# MRCS_ANIMATION-CONTROLLER.net
KiCad netlist of a schematic drawn in EAGLE
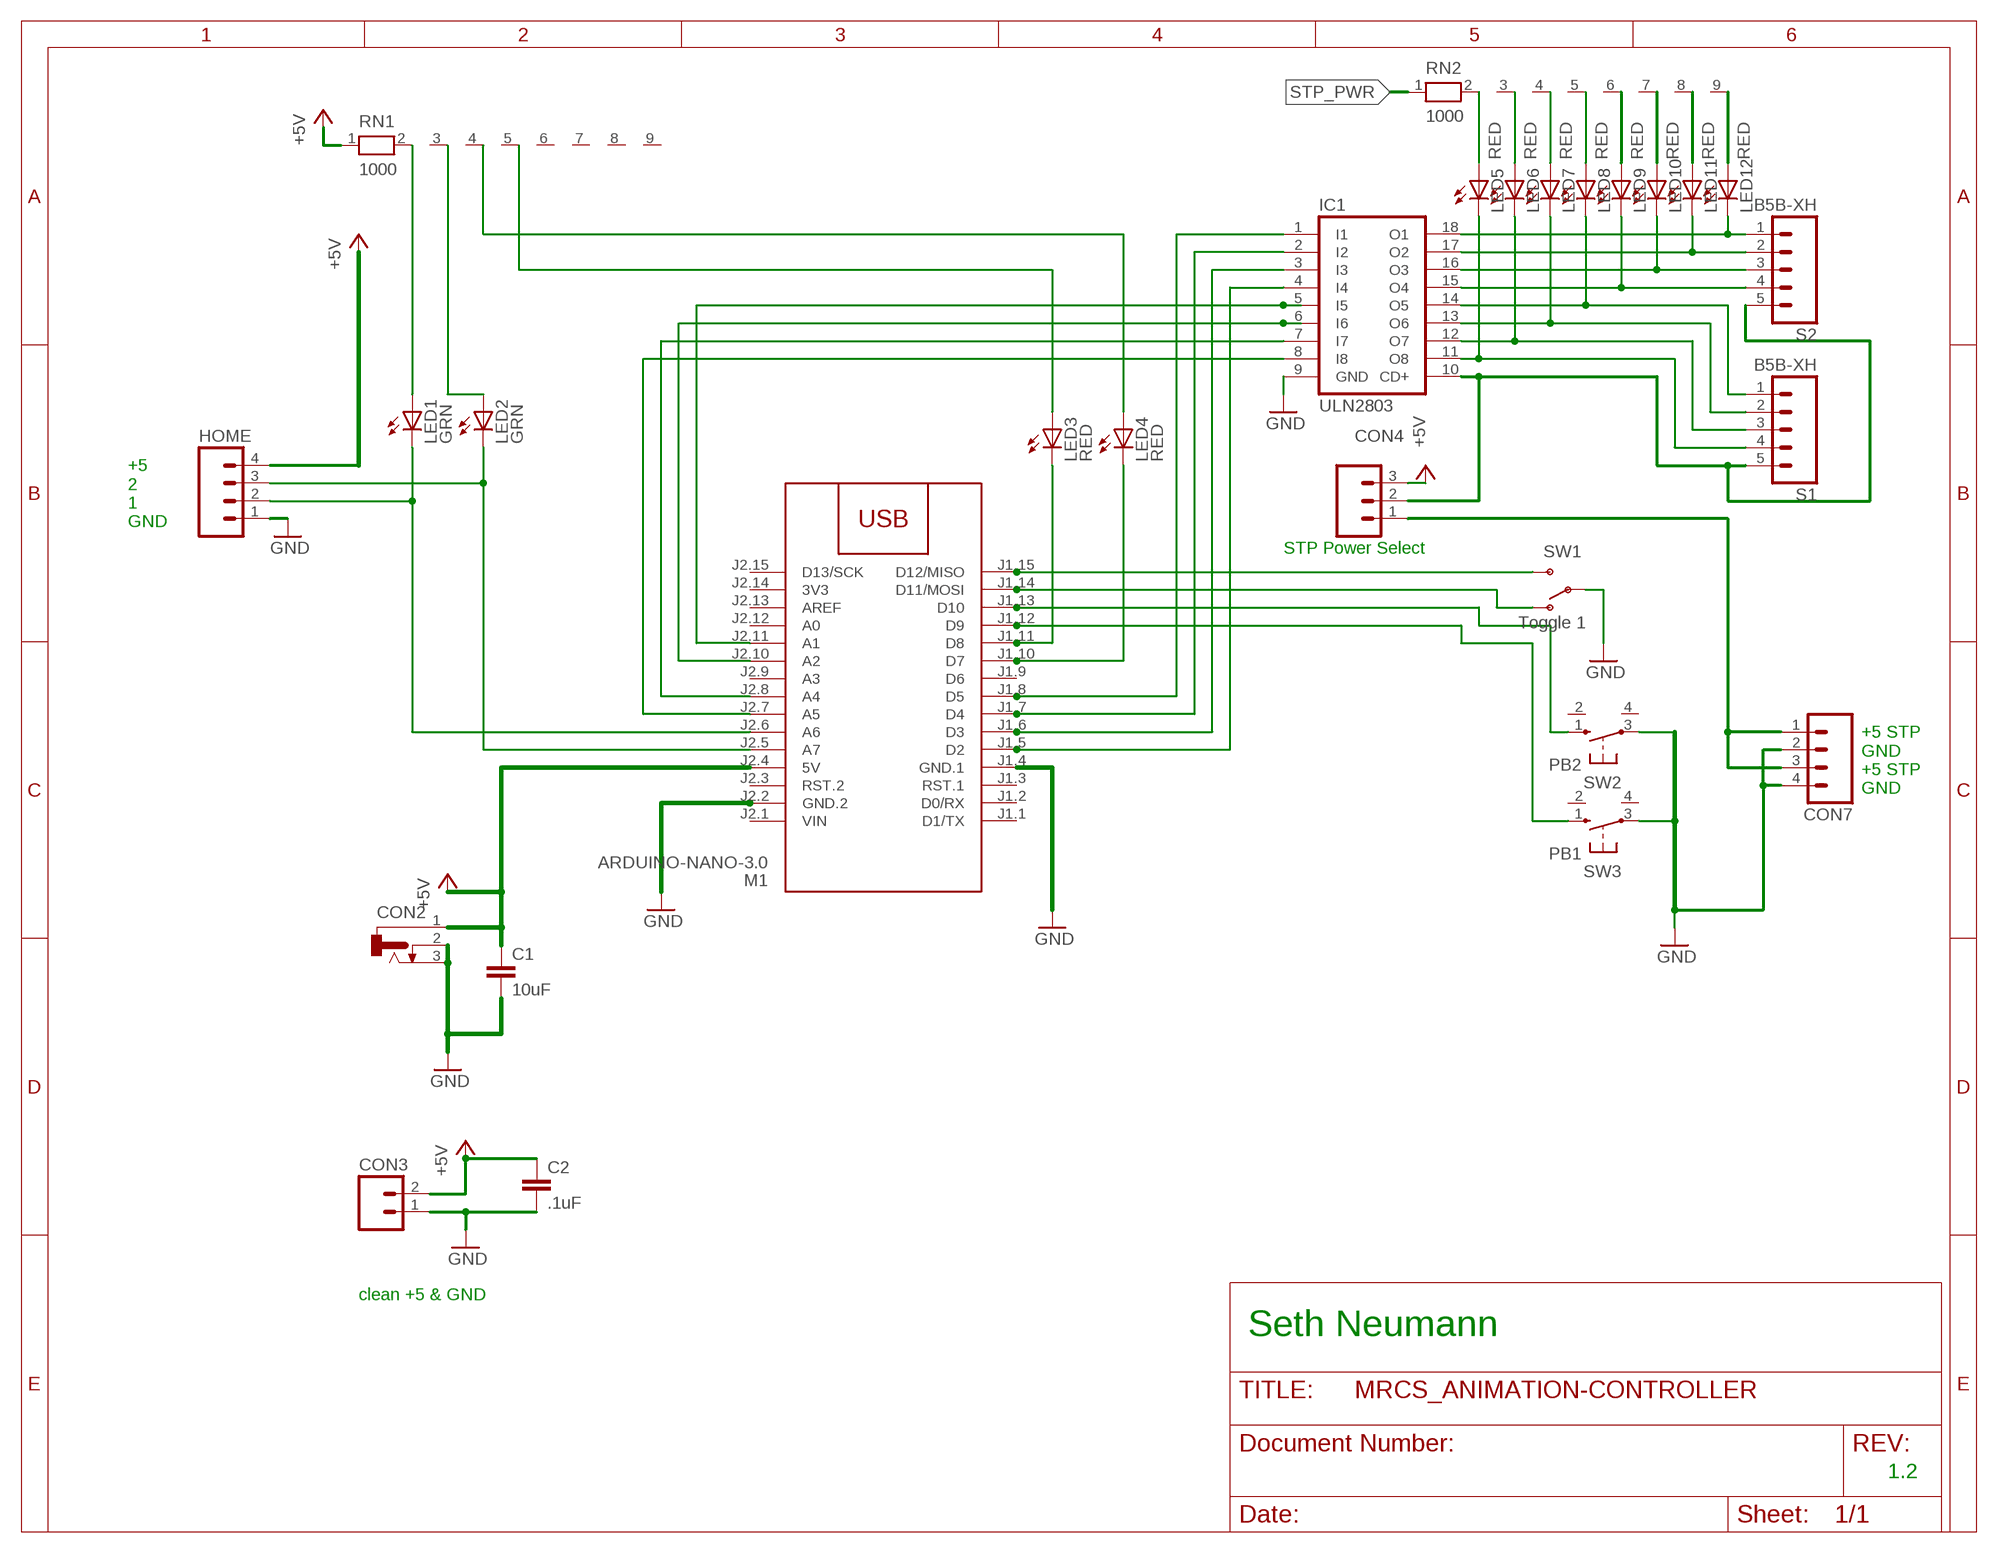
[diagram p0: schematic, sheet 1]

(export (version "E")
  (design (tool "Eeschema 10.0.6"))
  (components
    (comp (ref "C1")
      (value "10uF")
      (footprint "eagle-import:C5B3")
      (libsource (lib "eagle-import") (part "C5/3"))
    )
    (comp (ref "C2")
      (value ".1uF")
      (footprint "eagle-import:C5B3")
      (libsource (lib "eagle-import") (part "C5/3"))
    )
    (comp (ref "CON2")
      (value "CONNECTOR-DC-POWER-RA")
      (footprint "eagle-import:DCJ0202")
      (libsource (lib "eagle-import") (part "CONNECTOR-DC-POWER-RA"))
    )
    (comp (ref "CON3")
      (value "CONNECTOR-M02350-LOCK")
      (footprint "eagle-import:1751248")
      (libsource (lib "eagle-import") (part "CONNECTOR-M02350-LOCK"))
    )
    (comp (ref "CON4")
      (value "CONNECTOR-M03254-LOCK")
      (footprint "eagle-import:3POL254")
      (libsource (lib "eagle-import") (part "CONNECTOR-M03254-LOCK"))
    )
    (comp (ref "CON7")
      (value "CONNECTOR-M04SCREW_LOCK")
      (footprint "eagle-import:SCREWTERMINAL-3.5MM-4_LOCK")
      (libsource (lib "eagle-import") (part "CONNECTOR-M04SCREW_LOCK"))
    )
    (comp (ref "HOME")
      (value "CONNECTOR-M04LOCK")
      (footprint "eagle-import:1X04_LOCK")
      (libsource (lib "eagle-import") (part "CONNECTOR-M04LOCK"))
    )
    (comp (ref "IC1")
      (value "ULN2803")
      (footprint "eagle-import:DIL18")
      (libsource (lib "eagle-import") (part "ULN2803A"))
    )
    (comp (ref "LED1")
      (value "GRN")
      (footprint "eagle-import:LED3MM")
      (libsource (lib "eagle-import") (part "LEDLED3MM"))
    )
    (comp (ref "LED2")
      (value "GRN")
      (footprint "eagle-import:LED3MM")
      (libsource (lib "eagle-import") (part "LEDLED3MM"))
    )
    (comp (ref "LED3")
      (value "RED")
      (footprint "eagle-import:LED3MM")
      (libsource (lib "eagle-import") (part "LEDLED3MM"))
    )
    (comp (ref "LED4")
      (value "RED")
      (footprint "eagle-import:LED3MM")
      (libsource (lib "eagle-import") (part "LEDLED3MM"))
    )
    (comp (ref "LED5")
      (value "RED")
      (footprint "eagle-import:LED3MM")
      (libsource (lib "eagle-import") (part "LEDLED3MM"))
    )
    (comp (ref "LED6")
      (value "RED")
      (footprint "eagle-import:LED3MM")
      (libsource (lib "eagle-import") (part "LEDLED3MM"))
    )
    (comp (ref "LED7")
      (value "RED")
      (footprint "eagle-import:LED3MM")
      (libsource (lib "eagle-import") (part "LEDLED3MM"))
    )
    (comp (ref "LED8")
      (value "RED")
      (footprint "eagle-import:LED3MM")
      (libsource (lib "eagle-import") (part "LEDLED3MM"))
    )
    (comp (ref "LED9")
      (value "RED")
      (footprint "eagle-import:LED3MM")
      (libsource (lib "eagle-import") (part "LEDLED3MM"))
    )
    (comp (ref "LED10")
      (value "RED")
      (footprint "eagle-import:LED3MM")
      (libsource (lib "eagle-import") (part "LEDLED3MM"))
    )
    (comp (ref "LED11")
      (value "RED")
      (footprint "eagle-import:LED3MM")
      (libsource (lib "eagle-import") (part "LEDLED3MM"))
    )
    (comp (ref "LED12")
      (value "RED")
      (footprint "eagle-import:LED3MM")
      (libsource (lib "eagle-import") (part "LEDLED3MM"))
    )
    (comp (ref "M1")
      (value "ARDUINO-NANO-3.0")
      (footprint "eagle-import:ARDUINO-NANO-3.0")
      (libsource (lib "eagle-import") (part "ARDUINO-NANO-3.0"))
    )
    (comp (ref "RN1")
      (value "1000")
      (footprint "eagle-import:RN-9")
      (libsource (lib "eagle-import") (part "RN08"))
    )
    (comp (ref "RN2")
      (value "1000")
      (footprint "eagle-import:RN-9")
      (libsource (lib "eagle-import") (part "RN08"))
    )
    (comp (ref "S1")
      (value "B5B-XH")
      (footprint "eagle-import:1X05_LOCK")
      (libsource (lib "eagle-import") (part "CONNECTOR-M05LOCK"))
    )
    (comp (ref "S2")
      (value "B5B-XH")
      (footprint "eagle-import:1X05_LOCK")
      (libsource (lib "eagle-import") (part "CONNECTOR-M05LOCK"))
    )
    (comp (ref "SW1")
      (value "Toggle 1")
      (footprint "eagle-import:SWITCH-SPDT-508")
      (libsource (lib "eagle-import") (part "SWITCH-SPSTPTH-508"))
    )
    (comp (ref "SW2")
      (value "PB2")
      (footprint "eagle-import:4P-PTH-6.0X6.0X5.0H")
      (libsource (lib "eagle-import") (part "SWITCH-(ON)SMALLPADS"))
    )
    (comp (ref "SW3")
      (value "PB1")
      (footprint "eagle-import:4P-PTH-6.0X6.0X5.0H")
      (libsource (lib "eagle-import") (part "SWITCH-(ON)SMALLPADS"))
    )
  )
  (nets
    (net (code "1") (name "+5V") (class "Default")
      (node (ref "C1") (pin "1") (pinfunction "1_1") (pintype "passive"))
      (node (ref "C2") (pin "1") (pinfunction "1_1") (pintype "passive"))
      (node (ref "CON2") (pin "1") (pinfunction "1_1") (pintype "passive"))
      (node (ref "CON3") (pin "2") (pinfunction "B_2") (pintype "passive"))
      (node (ref "CON4") (pin "3") (pinfunction "3_3") (pintype "passive"))
      (node (ref "HOME") (pin "4") (pinfunction "4_4") (pintype "passive"))
      (node (ref "M1") (pin "J2.4") (pinfunction "5V_J2.4") (pintype "power_in"))
      (node (ref "RN1") (pin "1") (pinfunction "1_1") (pintype "passive"))
    )
    (net (code "2") (name "/3V3") (class "Default")
      (node (ref "M1") (pin "J2.14") (pinfunction "3V3_J2.14") (pintype "power_in"))
    )
    (net (code "3") (name "/VIN") (class "Default")
      (node (ref "M1") (pin "J2.1") (pinfunction "VIN_J2.1") (pintype "power_in"))
    )
    (net (code "4") (name "GND") (class "Default")
      (node (ref "C1") (pin "2") (pinfunction "2_2") (pintype "passive"))
      (node (ref "C2") (pin "2") (pinfunction "2_2") (pintype "passive"))
      (node (ref "CON2") (pin "2") (pinfunction "2_2") (pintype "passive"))
      (node (ref "CON2") (pin "3") (pinfunction "3_3") (pintype "passive"))
      (node (ref "CON3") (pin "1") (pinfunction "A_1") (pintype "passive"))
      (node (ref "CON7") (pin "2") (pinfunction "2_2") (pintype "passive"))
      (node (ref "CON7") (pin "4") (pinfunction "4_4") (pintype "passive"))
      (node (ref "HOME") (pin "1") (pinfunction "1_1") (pintype "passive"))
      (node (ref "IC1") (pin "9") (pinfunction "GND_9") (pintype "power_in"))
      (node (ref "M1") (pin "J1.4") (pinfunction "GND.1_J1.4") (pintype "power_in"))
      (node (ref "M1") (pin "J2.2") (pinfunction "GND.2_J2.2") (pintype "power_in"))
      (node (ref "SW1") (pin "2") (pinfunction "P_2") (pintype "passive"))
      (node (ref "SW2") (pin "3") (pinfunction "P_3") (pintype "passive"))
      (node (ref "SW3") (pin "3") (pinfunction "P_3") (pintype "passive"))
    )
    (net (code "5") (name "Net-(CON4-Pad1)") (class "Default")
      (node (ref "CON4") (pin "1") (pinfunction "1_1") (pintype "passive"))
      (node (ref "CON7") (pin "1") (pinfunction "1_1") (pintype "passive"))
      (node (ref "CON7") (pin "3") (pinfunction "3_3") (pintype "passive"))
    )
    (net (code "6") (name "Net-(IC1-I1)") (class "Default")
      (node (ref "IC1") (pin "1") (pinfunction "I1_1") (pintype "input"))
      (node (ref "M1") (pin "J1.8") (pinfunction "D5_J1.8") (pintype "bidirectional"))
    )
    (net (code "7") (name "Net-(IC1-I2)") (class "Default")
      (node (ref "IC1") (pin "2") (pinfunction "I2_2") (pintype "input"))
      (node (ref "M1") (pin "J1.7") (pinfunction "D4_J1.7") (pintype "bidirectional"))
    )
    (net (code "8") (name "Net-(IC1-I3)") (class "Default")
      (node (ref "IC1") (pin "3") (pinfunction "I3_3") (pintype "input"))
      (node (ref "M1") (pin "J1.6") (pinfunction "D3_J1.6") (pintype "bidirectional"))
    )
    (net (code "9") (name "Net-(IC1-I4)") (class "Default")
      (node (ref "IC1") (pin "4") (pinfunction "I4_4") (pintype "input"))
      (node (ref "M1") (pin "J1.5") (pinfunction "D2_J1.5") (pintype "bidirectional"))
    )
    (net (code "10") (name "Net-(IC1-I5)") (class "Default")
      (node (ref "IC1") (pin "5") (pinfunction "I5_5") (pintype "input"))
      (node (ref "M1") (pin "J2.11") (pinfunction "A1_J2.11") (pintype "bidirectional"))
    )
    (net (code "11") (name "Net-(IC1-I6)") (class "Default")
      (node (ref "IC1") (pin "6") (pinfunction "I6_6") (pintype "input"))
      (node (ref "M1") (pin "J2.10") (pinfunction "A2_J2.10") (pintype "bidirectional"))
    )
    (net (code "12") (name "Net-(IC1-I7)") (class "Default")
      (node (ref "IC1") (pin "7") (pinfunction "I7_7") (pintype "input"))
      (node (ref "M1") (pin "J2.8") (pinfunction "A4_J2.8") (pintype "bidirectional"))
    )
    (net (code "13") (name "Net-(IC1-I8)") (class "Default")
      (node (ref "IC1") (pin "8") (pinfunction "I8_8") (pintype "input"))
      (node (ref "M1") (pin "J2.7") (pinfunction "A5_J2.7") (pintype "bidirectional"))
    )
    (net (code "14") (name "Net-(IC1-O1)") (class "Default")
      (node (ref "IC1") (pin "18") (pinfunction "O1_18") (pintype "open_collector"))
      (node (ref "LED12") (pin "K") (pinfunction "C_K") (pintype "passive"))
      (node (ref "S2") (pin "1") (pinfunction "1_1") (pintype "passive"))
    )
    (net (code "15") (name "Net-(IC1-O2)") (class "Default")
      (node (ref "IC1") (pin "17") (pinfunction "O2_17") (pintype "open_collector"))
      (node (ref "LED11") (pin "K") (pinfunction "C_K") (pintype "passive"))
      (node (ref "S2") (pin "2") (pinfunction "2_2") (pintype "passive"))
    )
    (net (code "16") (name "Net-(IC1-O3)") (class "Default")
      (node (ref "IC1") (pin "16") (pinfunction "O3_16") (pintype "open_collector"))
      (node (ref "LED10") (pin "K") (pinfunction "C_K") (pintype "passive"))
      (node (ref "S2") (pin "3") (pinfunction "3_3") (pintype "passive"))
    )
    (net (code "17") (name "Net-(IC1-O4)") (class "Default")
      (node (ref "IC1") (pin "15") (pinfunction "O4_15") (pintype "open_collector"))
      (node (ref "LED9") (pin "K") (pinfunction "C_K") (pintype "passive"))
      (node (ref "S2") (pin "4") (pinfunction "4_4") (pintype "passive"))
    )
    (net (code "18") (name "Net-(IC1-O5)") (class "Default")
      (node (ref "IC1") (pin "14") (pinfunction "O5_14") (pintype "open_collector"))
      (node (ref "LED8") (pin "K") (pinfunction "C_K") (pintype "passive"))
      (node (ref "S1") (pin "1") (pinfunction "1_1") (pintype "passive"))
    )
    (net (code "19") (name "Net-(IC1-O6)") (class "Default")
      (node (ref "IC1") (pin "13") (pinfunction "O6_13") (pintype "open_collector"))
      (node (ref "LED7") (pin "K") (pinfunction "C_K") (pintype "passive"))
      (node (ref "S1") (pin "2") (pinfunction "2_2") (pintype "passive"))
    )
    (net (code "20") (name "Net-(IC1-O7)") (class "Default")
      (node (ref "IC1") (pin "12") (pinfunction "O7_12") (pintype "open_collector"))
      (node (ref "LED6") (pin "K") (pinfunction "C_K") (pintype "passive"))
      (node (ref "S1") (pin "3") (pinfunction "3_3") (pintype "passive"))
    )
    (net (code "21") (name "Net-(IC1-O8)") (class "Default")
      (node (ref "IC1") (pin "11") (pinfunction "O8_11") (pintype "open_collector"))
      (node (ref "LED5") (pin "K") (pinfunction "C_K") (pintype "passive"))
      (node (ref "S1") (pin "4") (pinfunction "4_4") (pintype "passive"))
    )
    (net (code "22") (name "Net-(LED1-C)") (class "Default")
      (node (ref "HOME") (pin "2") (pinfunction "2_2") (pintype "passive"))
      (node (ref "LED1") (pin "K") (pinfunction "C_K") (pintype "passive"))
      (node (ref "M1") (pin "J2.6") (pinfunction "A6_J2.6") (pintype "bidirectional"))
    )
    (net (code "23") (name "Net-(LED1-PadA)") (class "Default")
      (node (ref "LED1") (pin "A") (pinfunction "A_A") (pintype "passive"))
      (node (ref "RN1") (pin "2") (pinfunction "2_2") (pintype "passive"))
    )
    (net (code "24") (name "Net-(LED2-C)") (class "Default")
      (node (ref "HOME") (pin "3") (pinfunction "3_3") (pintype "passive"))
      (node (ref "LED2") (pin "K") (pinfunction "C_K") (pintype "passive"))
      (node (ref "M1") (pin "J2.5") (pinfunction "A7_J2.5") (pintype "bidirectional"))
    )
    (net (code "25") (name "Net-(LED2-PadA)") (class "Default")
      (node (ref "LED2") (pin "A") (pinfunction "A_A") (pintype "passive"))
      (node (ref "RN1") (pin "3") (pinfunction "3_3") (pintype "passive"))
    )
    (net (code "26") (name "Net-(LED3-C)") (class "Default")
      (node (ref "LED3") (pin "K") (pinfunction "C_K") (pintype "passive"))
      (node (ref "M1") (pin "J1.11") (pinfunction "D8_J1.11") (pintype "bidirectional"))
    )
    (net (code "27") (name "Net-(LED3-PadA)") (class "Default")
      (node (ref "LED3") (pin "A") (pinfunction "A_A") (pintype "passive"))
      (node (ref "RN1") (pin "5") (pinfunction "5_5") (pintype "passive"))
    )
    (net (code "28") (name "Net-(LED4-C)") (class "Default")
      (node (ref "LED4") (pin "K") (pinfunction "C_K") (pintype "passive"))
      (node (ref "M1") (pin "J1.10") (pinfunction "D7_J1.10") (pintype "bidirectional"))
    )
    (net (code "29") (name "Net-(LED4-PadA)") (class "Default")
      (node (ref "LED4") (pin "A") (pinfunction "A_A") (pintype "passive"))
      (node (ref "RN1") (pin "4") (pinfunction "4_4") (pintype "passive"))
    )
    (net (code "30") (name "Net-(LED5-PadA)") (class "Default")
      (node (ref "LED5") (pin "A") (pinfunction "A_A") (pintype "passive"))
      (node (ref "RN2") (pin "2") (pinfunction "2_2") (pintype "passive"))
    )
    (net (code "31") (name "Net-(LED6-PadA)") (class "Default")
      (node (ref "LED6") (pin "A") (pinfunction "A_A") (pintype "passive"))
      (node (ref "RN2") (pin "3") (pinfunction "3_3") (pintype "passive"))
    )
    (net (code "32") (name "Net-(LED7-PadA)") (class "Default")
      (node (ref "LED7") (pin "A") (pinfunction "A_A") (pintype "passive"))
      (node (ref "RN2") (pin "4") (pinfunction "4_4") (pintype "passive"))
    )
    (net (code "33") (name "Net-(LED8-PadA)") (class "Default")
      (node (ref "LED8") (pin "A") (pinfunction "A_A") (pintype "passive"))
      (node (ref "RN2") (pin "5") (pinfunction "5_5") (pintype "passive"))
    )
    (net (code "34") (name "Net-(LED9-PadA)") (class "Default")
      (node (ref "LED9") (pin "A") (pinfunction "A_A") (pintype "passive"))
      (node (ref "RN2") (pin "6") (pinfunction "6_6") (pintype "passive"))
    )
    (net (code "35") (name "Net-(LED10-PadA)") (class "Default")
      (node (ref "LED10") (pin "A") (pinfunction "A_A") (pintype "passive"))
      (node (ref "RN2") (pin "7") (pinfunction "7_7") (pintype "passive"))
    )
    (net (code "36") (name "Net-(LED11-PadA)") (class "Default")
      (node (ref "LED11") (pin "A") (pinfunction "A_A") (pintype "passive"))
      (node (ref "RN2") (pin "8") (pinfunction "8_8") (pintype "passive"))
    )
    (net (code "37") (name "Net-(LED12-PadA)") (class "Default")
      (node (ref "LED12") (pin "A") (pinfunction "A_A") (pintype "passive"))
      (node (ref "RN2") (pin "9") (pinfunction "9_9") (pintype "passive"))
    )
    (net (code "38") (name "Net-(M1-D9)") (class "Default")
      (node (ref "M1") (pin "J1.12") (pinfunction "D9_J1.12") (pintype "bidirectional"))
      (node (ref "SW3") (pin "1") (pinfunction "S_1") (pintype "passive"))
    )
    (net (code "39") (name "Net-(M1-D10)") (class "Default")
      (node (ref "M1") (pin "J1.13") (pinfunction "D10_J1.13") (pintype "bidirectional"))
      (node (ref "SW2") (pin "1") (pinfunction "S_1") (pintype "passive"))
    )
    (net (code "40") (name "Net-(M1-D11{slash}MOSI)") (class "Default")
      (node (ref "M1") (pin "J1.14") (pinfunction "D11/MOSI_J1.14") (pintype "bidirectional"))
      (node (ref "SW1") (pin "1") (pinfunction "O_1") (pintype "passive"))
    )
    (net (code "41") (name "Net-(M1-D12{slash}MISO)") (class "Default")
      (node (ref "M1") (pin "J1.15") (pinfunction "D12/MISO_J1.15") (pintype "bidirectional"))
      (node (ref "SW1") (pin "3") (pinfunction "S_3") (pintype "passive"))
    )
    (net (code "42") (name "STP_PWR") (class "Default")
      (node (ref "CON4") (pin "2") (pinfunction "2_2") (pintype "passive"))
      (node (ref "IC1") (pin "10") (pinfunction "CD+_10") (pintype "passive"))
      (node (ref "RN2") (pin "1") (pinfunction "1_1") (pintype "passive"))
      (node (ref "S1") (pin "5") (pinfunction "5_5") (pintype "passive"))
      (node (ref "S2") (pin "5") (pinfunction "5_5") (pintype "passive"))
    )
    (net (code "43") (name "unconnected-(M1-A0-PadJ2.12)") (class "Default")
      (node (ref "M1") (pin "J2.12") (pinfunction "A0_J2.12") (pintype "bidirectional"))
    )
    (net (code "44") (name "unconnected-(M1-A3-PadJ2.9)") (class "Default")
      (node (ref "M1") (pin "J2.9") (pinfunction "A3_J2.9") (pintype "bidirectional"))
    )
    (net (code "45") (name "unconnected-(M1-AREF-PadJ2.13)") (class "Default")
      (node (ref "M1") (pin "J2.13") (pinfunction "AREF_J2.13") (pintype "bidirectional"))
    )
    (net (code "46") (name "unconnected-(M1-D0{slash}RX-PadJ1.2)") (class "Default")
      (node (ref "M1") (pin "J1.2") (pinfunction "D0/RX_J1.2") (pintype "bidirectional"))
    )
    (net (code "47") (name "unconnected-(M1-D1{slash}TX-PadJ1.1)") (class "Default")
      (node (ref "M1") (pin "J1.1") (pinfunction "D1/TX_J1.1") (pintype "bidirectional"))
    )
    (net (code "48") (name "unconnected-(M1-D6-PadJ1.9)") (class "Default")
      (node (ref "M1") (pin "J1.9") (pinfunction "D6_J1.9") (pintype "bidirectional"))
    )
    (net (code "49") (name "unconnected-(M1-D13{slash}SCK-PadJ2.15)") (class "Default")
      (node (ref "M1") (pin "J2.15") (pinfunction "D13/SCK_J2.15") (pintype "bidirectional"))
    )
    (net (code "50") (name "unconnected-(M1-RST.1-PadJ1.3)") (class "Default")
      (node (ref "M1") (pin "J1.3") (pinfunction "RST.1_J1.3") (pintype "bidirectional"))
    )
    (net (code "51") (name "unconnected-(M1-RST.2-PadJ2.3)") (class "Default")
      (node (ref "M1") (pin "J2.3") (pinfunction "RST.2_J2.3") (pintype "bidirectional"))
    )
    (net (code "52") (name "unconnected-(RN1-Pad6)") (class "Default")
      (node (ref "RN1") (pin "6") (pinfunction "6_6") (pintype "passive"))
    )
    (net (code "53") (name "unconnected-(RN1-Pad7)") (class "Default")
      (node (ref "RN1") (pin "7") (pinfunction "7_7") (pintype "passive"))
    )
    (net (code "54") (name "unconnected-(RN1-Pad8)") (class "Default")
      (node (ref "RN1") (pin "8") (pinfunction "8_8") (pintype "passive"))
    )
    (net (code "55") (name "unconnected-(RN1-Pad9)") (class "Default")
      (node (ref "RN1") (pin "9") (pinfunction "9_9") (pintype "passive"))
    )
    (net (code "56") (name "unconnected-(SW2-P1-Pad4)") (class "Default")
      (node (ref "SW2") (pin "4") (pinfunction "P1_4") (pintype "passive"))
    )
    (net (code "57") (name "unconnected-(SW2-S1-Pad2)") (class "Default")
      (node (ref "SW2") (pin "2") (pinfunction "S1_2") (pintype "passive"))
    )
    (net (code "58") (name "unconnected-(SW3-P1-Pad4)") (class "Default")
      (node (ref "SW3") (pin "4") (pinfunction "P1_4") (pintype "passive"))
    )
    (net (code "59") (name "unconnected-(SW3-S1-Pad2)") (class "Default")
      (node (ref "SW3") (pin "2") (pinfunction "S1_2") (pintype "passive"))
    )
  )
)
